# Nucleo.net
KiCad netlist of a schematic drawn in Altium Designer
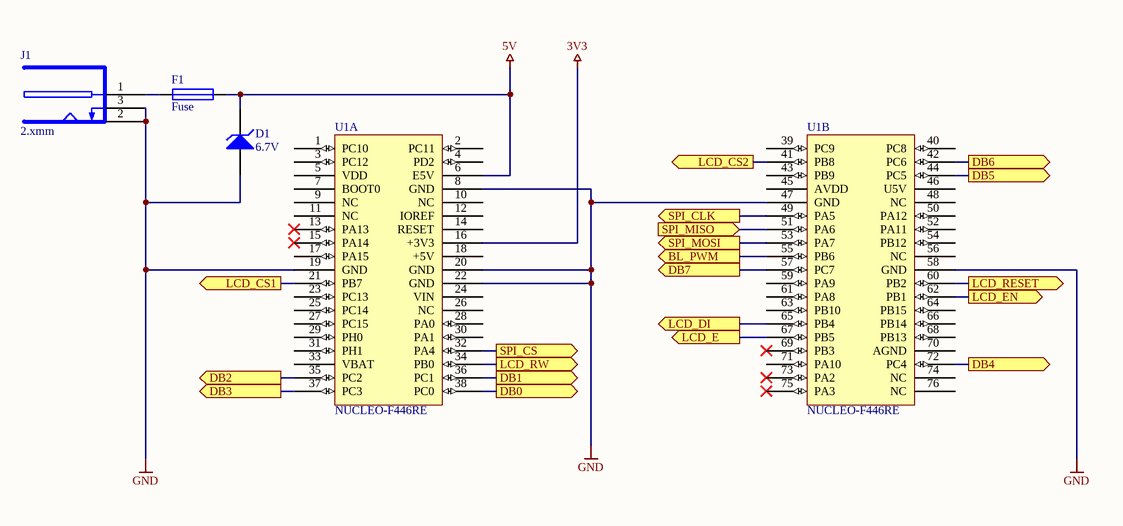
[diagram p0: Nucleo.SchDoc]

(export (version "E")
  (design (tool "Eeschema 10.0.6"))
  (components
    (comp (ref "D1")
      (value "6.7V")
      (footprint "FP_SMA")
      (description "Zener Diode")
      (libsource (lib "hallglib") (part "ZENER"))
    )
    (comp (ref "F1") (value "Fuse") (footprint "FP_MULTIFUSE") (libsource (lib "hallglib") (part "Fuse")))
    (comp (ref "J1")
      (value "2.xmm")
      (footprint "FP_DC_TAP_ANYA")
      (description "2.xmm DC HEBA25 TÁPFESZÜLTSÉG ALJZAT ZÁRT, NYÁKBA 90°")
      (libsource (lib "hallglib") (part "DC_TAP_ANYA"))
    )
    (comp (ref "U1")
      (value "NUCLEO-F446RE")
      (footprint "FP_NUCLEO-64_2x20")
      (libsource (lib "hallglib") (part "NUCLEO-F446RE"))
    )
  )
  (nets
    (net (code "1") (name "/BL_PWM") (class "Default")
      (node (ref "U1") (pin "55") (pinfunction "PB6_55") (pintype "bidirectional"))
    )
    (net (code "2") (name "/DB0") (class "Default")
      (node (ref "U1") (pin "38") (pinfunction "PC0_38") (pintype "bidirectional"))
    )
    (net (code "3") (name "/DB1") (class "Default")
      (node (ref "U1") (pin "36") (pinfunction "PC1_36") (pintype "bidirectional"))
    )
    (net (code "4") (name "/DB2") (class "Default")
      (node (ref "U1") (pin "35") (pinfunction "PC2_35") (pintype "bidirectional"))
    )
    (net (code "5") (name "/DB3") (class "Default")
      (node (ref "U1") (pin "37") (pinfunction "PC3_37") (pintype "bidirectional"))
    )
    (net (code "6") (name "/DB4") (class "Default")
      (node (ref "U1") (pin "72") (pinfunction "PC4_72") (pintype "bidirectional"))
    )
    (net (code "7") (name "/DB5") (class "Default")
      (node (ref "U1") (pin "44") (pinfunction "PC5_44") (pintype "bidirectional"))
    )
    (net (code "8") (name "/DB6") (class "Default")
      (node (ref "U1") (pin "42") (pinfunction "PC6_42") (pintype "bidirectional"))
    )
    (net (code "9") (name "/DB7") (class "Default")
      (node (ref "U1") (pin "57") (pinfunction "PC7_57") (pintype "bidirectional"))
    )
    (net (code "10") (name "/LCD_CS1") (class "Default")
      (node (ref "U1") (pin "21") (pinfunction "PB7_21") (pintype "bidirectional"))
    )
    (net (code "11") (name "/LCD_CS2") (class "Default")
      (node (ref "U1") (pin "41") (pinfunction "PB8_41") (pintype "bidirectional"))
    )
    (net (code "12") (name "/LCD_DI") (class "Default")
      (node (ref "U1") (pin "65") (pinfunction "PB4_65") (pintype "bidirectional"))
    )
    (net (code "13") (name "/LCD_E") (class "Default")
      (node (ref "U1") (pin "67") (pinfunction "PB5_67") (pintype "bidirectional"))
    )
    (net (code "14") (name "/LCD_EN") (class "Default")
      (node (ref "U1") (pin "62") (pinfunction "PB1_62") (pintype "bidirectional"))
    )
    (net (code "15") (name "/LCD_RESET") (class "Default")
      (node (ref "U1") (pin "60") (pinfunction "PB2_60") (pintype "bidirectional"))
    )
    (net (code "16") (name "/LCD_RW") (class "Default")
      (node (ref "U1") (pin "34") (pinfunction "PB0_34") (pintype "bidirectional"))
    )
    (net (code "17") (name "/SPI_CLK") (class "Default")
      (node (ref "U1") (pin "49") (pinfunction "PA5_49") (pintype "bidirectional"))
    )
    (net (code "18") (name "/SPI_CS") (class "Default")
      (node (ref "U1") (pin "32") (pinfunction "PA4_32") (pintype "bidirectional"))
    )
    (net (code "19") (name "/SPI_MISO") (class "Default")
      (node (ref "U1") (pin "51") (pinfunction "PA6_51") (pintype "bidirectional"))
    )
    (net (code "20") (name "/SPI_MOSI") (class "Default")
      (node (ref "U1") (pin "53") (pinfunction "PA7_53") (pintype "bidirectional"))
    )
    (net (code "21") (name "3V3") (class "Default")
      (node (ref "U1") (pin "16") (pinfunction "+3V3_16") (pintype "power_in"))
    )
    (net (code "22") (name "5V") (class "Default")
      (node (ref "D1") (pin "2") (pinfunction "K_2") (pintype "passive"))
      (node (ref "F1") (pin "2") (pinfunction "2_2") (pintype "passive"))
      (node (ref "U1") (pin "6") (pinfunction "E5V_6") (pintype "power_in"))
    )
    (net (code "23") (name "GND") (class "Default")
      (node (ref "D1") (pin "1") (pinfunction "A_1") (pintype "passive"))
      (node (ref "J1") (pin "2") (pinfunction "SLEEVE_2") (pintype "power_in"))
      (node (ref "J1") (pin "3") (pinfunction "BREAK_3") (pintype "power_in"))
      (node (ref "U1") (pin "19") (pinfunction "GND_19") (pintype "passive"))
      (node (ref "U1") (pin "20") (pinfunction "GND_20") (pintype "passive"))
      (node (ref "U1") (pin "22") (pinfunction "GND_22") (pintype "passive"))
      (node (ref "U1") (pin "47") (pinfunction "GND_47") (pintype "passive"))
      (node (ref "U1") (pin "58") (pinfunction "GND_58") (pintype "passive"))
      (node (ref "U1") (pin "8") (pinfunction "GND_8") (pintype "passive"))
    )
    (net (code "24") (name "Net-(J1-PIN)") (class "Default")
      (node (ref "F1") (pin "1") (pinfunction "1_1") (pintype "passive"))
      (node (ref "J1") (pin "1") (pinfunction "PIN_1") (pintype "power_in"))
    )
    (net (code "25") (name "unconnected-(U1A-+5V-Pad18)") (class "Default")
      (node (ref "U1") (pin "18") (pinfunction "+5V_18") (pintype "power_in"))
    )
    (net (code "26") (name "unconnected-(U1A-BOOT0-Pad7)") (class "Default")
      (node (ref "U1") (pin "7") (pinfunction "BOOT0_7") (pintype "passive"))
    )
    (net (code "27") (name "unconnected-(U1A-IOREF-Pad12)") (class "Default")
      (node (ref "U1") (pin "12") (pinfunction "IOREF_12") (pintype "passive"))
    )
    (net (code "28") (name "unconnected-(U1A-NC-Pad9)") (class "Default")
      (node (ref "U1") (pin "9") (pinfunction "NC_9") (pintype "passive"))
    )
    (net (code "29") (name "unconnected-(U1A-NC-Pad10)") (class "Default")
      (node (ref "U1") (pin "10") (pinfunction "NC_10") (pintype "passive"))
    )
    (net (code "30") (name "unconnected-(U1A-NC-Pad11)") (class "Default")
      (node (ref "U1") (pin "11") (pinfunction "NC_11") (pintype "passive"))
    )
    (net (code "31") (name "unconnected-(U1A-NC-Pad26)") (class "Default")
      (node (ref "U1") (pin "26") (pinfunction "NC_26") (pintype "passive"))
    )
    (net (code "32") (name "unconnected-(U1A-PA0-Pad28)") (class "Default")
      (node (ref "U1") (pin "28") (pinfunction "PA0_28") (pintype "bidirectional"))
    )
    (net (code "33") (name "unconnected-(U1A-PA1-Pad30)") (class "Default")
      (node (ref "U1") (pin "30") (pinfunction "PA1_30") (pintype "bidirectional"))
    )
    (net (code "34") (name "unconnected-(U1A-PA13-Pad13)") (class "Default")
      (node (ref "U1") (pin "13") (pinfunction "PA13_13") (pintype "bidirectional+no_connect"))
    )
    (net (code "35") (name "unconnected-(U1A-PA14-Pad15)") (class "Default")
      (node (ref "U1") (pin "15") (pinfunction "PA14_15") (pintype "bidirectional+no_connect"))
    )
    (net (code "36") (name "unconnected-(U1A-PA15-Pad17)") (class "Default")
      (node (ref "U1") (pin "17") (pinfunction "PA15_17") (pintype "bidirectional"))
    )
    (net (code "37") (name "unconnected-(U1A-PC10-Pad1)") (class "Default")
      (node (ref "U1") (pin "1") (pinfunction "PC10_1") (pintype "bidirectional"))
    )
    (net (code "38") (name "unconnected-(U1A-PC11-Pad2)") (class "Default")
      (node (ref "U1") (pin "2") (pinfunction "PC11_2") (pintype "bidirectional"))
    )
    (net (code "39") (name "unconnected-(U1A-PC12-Pad3)") (class "Default")
      (node (ref "U1") (pin "3") (pinfunction "PC12_3") (pintype "bidirectional"))
    )
    (net (code "40") (name "unconnected-(U1A-PC13-Pad23)") (class "Default")
      (node (ref "U1") (pin "23") (pinfunction "PC13_23") (pintype "bidirectional"))
    )
    (net (code "41") (name "unconnected-(U1A-PC14-Pad25)") (class "Default")
      (node (ref "U1") (pin "25") (pinfunction "PC14_25") (pintype "bidirectional"))
    )
    (net (code "42") (name "unconnected-(U1A-PC15-Pad27)") (class "Default")
      (node (ref "U1") (pin "27") (pinfunction "PC15_27") (pintype "bidirectional"))
    )
    (net (code "43") (name "unconnected-(U1A-PD2-Pad4)") (class "Default")
      (node (ref "U1") (pin "4") (pinfunction "PD2_4") (pintype "bidirectional"))
    )
    (net (code "44") (name "unconnected-(U1A-PH0-Pad29)") (class "Default")
      (node (ref "U1") (pin "29") (pinfunction "PH0_29") (pintype "bidirectional"))
    )
    (net (code "45") (name "unconnected-(U1A-PH1-Pad31)") (class "Default")
      (node (ref "U1") (pin "31") (pinfunction "PH1_31") (pintype "bidirectional"))
    )
    (net (code "46") (name "unconnected-(U1A-RESET-Pad14)") (class "Default")
      (node (ref "U1") (pin "14") (pinfunction "RESET_14") (pintype "passive"))
    )
    (net (code "47") (name "unconnected-(U1A-VBAT-Pad33)") (class "Default")
      (node (ref "U1") (pin "33") (pinfunction "VBAT_33") (pintype "power_in"))
    )
    (net (code "48") (name "unconnected-(U1A-VDD-Pad5)") (class "Default")
      (node (ref "U1") (pin "5") (pinfunction "VDD_5") (pintype "power_in"))
    )
    (net (code "49") (name "unconnected-(U1A-VIN-Pad24)") (class "Default")
      (node (ref "U1") (pin "24") (pinfunction "VIN_24") (pintype "power_in"))
    )
    (net (code "50") (name "unconnected-(U1B-AGND-Pad70)") (class "Default")
      (node (ref "U1") (pin "70") (pinfunction "AGND_70") (pintype "passive"))
    )
    (net (code "51") (name "unconnected-(U1B-AVDD-Pad45)") (class "Default")
      (node (ref "U1") (pin "45") (pinfunction "AVDD_45") (pintype "power_in"))
    )
    (net (code "52") (name "unconnected-(U1B-NC-Pad48)") (class "Default")
      (node (ref "U1") (pin "48") (pinfunction "NC_48") (pintype "passive"))
    )
    (net (code "53") (name "unconnected-(U1B-NC-Pad56)") (class "Default")
      (node (ref "U1") (pin "56") (pinfunction "NC_56") (pintype "passive"))
    )
    (net (code "54") (name "unconnected-(U1B-NC-Pad74)") (class "Default")
      (node (ref "U1") (pin "74") (pinfunction "NC_74") (pintype "passive"))
    )
    (net (code "55") (name "unconnected-(U1B-NC-Pad76)") (class "Default")
      (node (ref "U1") (pin "76") (pinfunction "NC_76") (pintype "passive"))
    )
    (net (code "56") (name "unconnected-(U1B-PA2-Pad73)") (class "Default")
      (node (ref "U1") (pin "73") (pinfunction "PA2_73") (pintype "bidirectional+no_connect"))
    )
    (net (code "57") (name "unconnected-(U1B-PA3-Pad75)") (class "Default")
      (node (ref "U1") (pin "75") (pinfunction "PA3_75") (pintype "bidirectional+no_connect"))
    )
    (net (code "58") (name "unconnected-(U1B-PA8-Pad61)") (class "Default")
      (node (ref "U1") (pin "61") (pinfunction "PA8_61") (pintype "bidirectional"))
    )
    (net (code "59") (name "unconnected-(U1B-PA9-Pad59)") (class "Default")
      (node (ref "U1") (pin "59") (pinfunction "PA9_59") (pintype "bidirectional"))
    )
    (net (code "60") (name "unconnected-(U1B-PA10-Pad71)") (class "Default")
      (node (ref "U1") (pin "71") (pinfunction "PA10_71") (pintype "bidirectional"))
    )
    (net (code "61") (name "unconnected-(U1B-PA11-Pad52)") (class "Default")
      (node (ref "U1") (pin "52") (pinfunction "PA11_52") (pintype "bidirectional"))
    )
    (net (code "62") (name "unconnected-(U1B-PA12-Pad50)") (class "Default")
      (node (ref "U1") (pin "50") (pinfunction "PA12_50") (pintype "bidirectional"))
    )
    (net (code "63") (name "unconnected-(U1B-PB3-Pad69)") (class "Default")
      (node (ref "U1") (pin "69") (pinfunction "PB3_69") (pintype "bidirectional+no_connect"))
    )
    (net (code "64") (name "unconnected-(U1B-PB9-Pad43)") (class "Default")
      (node (ref "U1") (pin "43") (pinfunction "PB9_43") (pintype "bidirectional"))
    )
    (net (code "65") (name "unconnected-(U1B-PB10-Pad63)") (class "Default")
      (node (ref "U1") (pin "63") (pinfunction "PB10_63") (pintype "bidirectional"))
    )
    (net (code "66") (name "unconnected-(U1B-PB12-Pad54)") (class "Default")
      (node (ref "U1") (pin "54") (pinfunction "PB12_54") (pintype "bidirectional"))
    )
    (net (code "67") (name "unconnected-(U1B-PB13-Pad68)") (class "Default")
      (node (ref "U1") (pin "68") (pinfunction "PB13_68") (pintype "bidirectional"))
    )
    (net (code "68") (name "unconnected-(U1B-PB14-Pad66)") (class "Default")
      (node (ref "U1") (pin "66") (pinfunction "PB14_66") (pintype "bidirectional"))
    )
    (net (code "69") (name "unconnected-(U1B-PB15-Pad64)") (class "Default")
      (node (ref "U1") (pin "64") (pinfunction "PB15_64") (pintype "bidirectional"))
    )
    (net (code "70") (name "unconnected-(U1B-PC8-Pad40)") (class "Default")
      (node (ref "U1") (pin "40") (pinfunction "PC8_40") (pintype "bidirectional"))
    )
    (net (code "71") (name "unconnected-(U1B-PC9-Pad39)") (class "Default")
      (node (ref "U1") (pin "39") (pinfunction "PC9_39") (pintype "bidirectional"))
    )
    (net (code "72") (name "unconnected-(U1B-U5V-Pad46)") (class "Default")
      (node (ref "U1") (pin "46") (pinfunction "U5V_46") (pintype "power_in"))
    )
  )
)
